# 08_-LoRa_RAK3172.net
KiCad netlist of a schematic drawn in Altium Designer
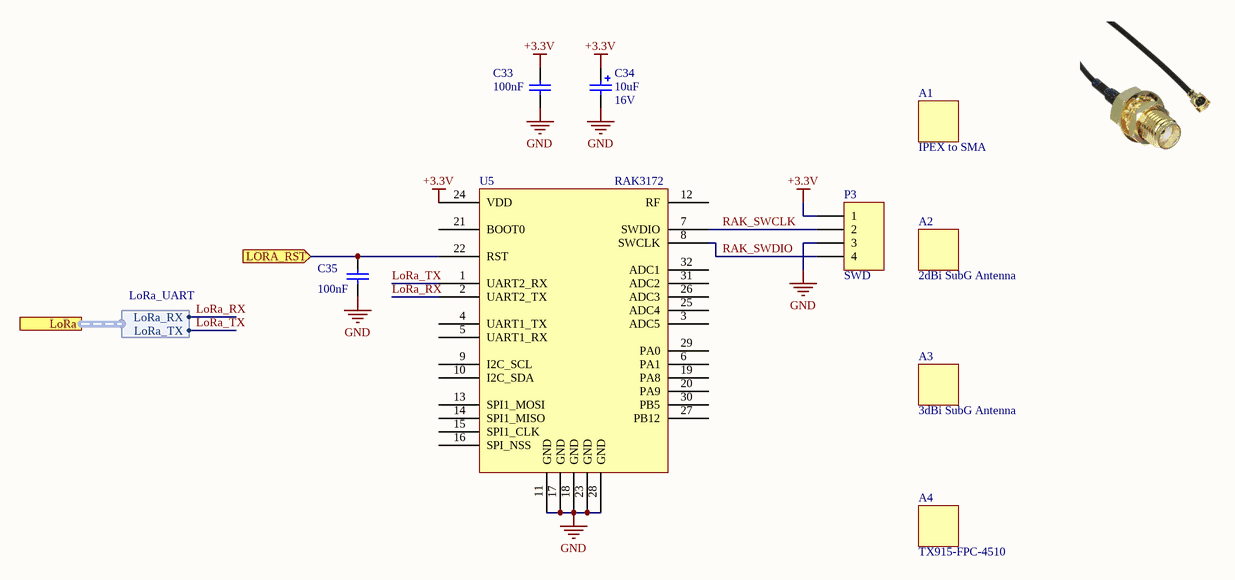
[diagram p0: [08] -LoRa_RAK3172.SchDoc]

(export (version "E")
  (design (tool "Eeschema 10.0.6"))
  (components
    (comp (ref "A1")
      (value "IPEX to SMA")
      (description "IPEX to SMA adapter cable")
      (libsource (lib "BaseNode v1.2") (part "Mechanical_component"))
    )
    (comp (ref "A2")
      (value "2dBi SubG Antenna")
      (libsource (lib "BaseNode v1.2") (part "Mechanical_component"))
    )
    (comp (ref "A3")
      (value "3dBi SubG Antenna")
      (libsource (lib "BaseNode v1.2") (part "Mechanical_component"))
    )
    (comp (ref "A4")
      (value "TX915-FPC-4510")
      (description "TX915-FPC-4510 868~930MHz adhesive antenna")
      (libsource (lib "BaseNode v1.2") (part "Mechanical_component"))
    )
    (comp (ref "C33")
      (value "Capacitor")
      (footprint "Cap 0603")
      (description "Cap Ceramic 0.1uF 50VDC X7R 10% SMD 0603 Paper T/R")
      (fields
        (field (name "MANUFACTURER") "Samsung")
        (field (name "MANUFACTURER PART NUMBER") "CL10B104KB8NNNC")
        (field (name "CAPACITANCE") "100nF")
      )
      (libsource (lib "Altium_Library") (part "Capacitor"))
    )
    (comp (ref "C34")
      (value "Capacitor Polarized")
      (footprint "Tantalum 3216 A")
      (description "CAP TANT 10UF 10% 16V 1206")
      (fields
        (field (name "MANUFACTURER") "Vishay Sprague")
        (field (name "MANUFACTURER PART NUMBER") "293D106X9016A2TE3")
        (field (name "CAPACITANCE") "10uF")
        (field (name "VOLTAGE RATING") "16V")
      )
      (libsource (lib "Altium_Library") (part "Capacitor Polarized"))
    )
    (comp (ref "C35")
      (value "Capacitor")
      (footprint "Cap 0603")
      (description "Cap Ceramic 0.1uF 50VDC X7R 10% SMD 0603 Paper T/R")
      (fields
        (field (name "MANUFACTURER") "Samsung")
        (field (name "MANUFACTURER PART NUMBER") "CL10B104KB8NNNC")
        (field (name "CAPACITANCE") "100nF")
      )
      (libsource (lib "Altium_Library") (part "Capacitor"))
    )
    (comp (ref "P3")
      (value "SWD")
      (footprint "HEADER SMD")
      (description "CONN HEADER VERT 4POS 2.54MM")
      (fields
        (field (name "MANUFACTURER") "Wurth Electronics")
        (field (name "MANUFACTURER PART NUMBER") "61300411121")
      )
      (libsource (lib "Altium_Library") (part "Header 4"))
    )
    (comp (ref "U5")
      (value "RAK3172")
      (footprint "RAK3172")
      (description "LPWAN Module")
      (libsource (lib "BaseNode v1.3") (part "RAK3172"))
    )
  )
  (nets
    (net (code "2") (name "+3.3V") (class "Default")
      (node (ref "C33") (pin "2") (pinfunction "2_2") (pintype "passive"))
      (node (ref "C34") (pin "1") (pinfunction "1_1") (pintype "passive"))
      (node (ref "P3") (pin "1") (pinfunction "1_1") (pintype "passive"))
      (node (ref "U5") (pin "24") (pinfunction "VDD_24") (pintype "passive"))
    )
    (net (code "3") (name "/LORA_RST") (class "Default")
      (node (ref "C35") (pin "2") (pinfunction "2_2") (pintype "passive"))
      (node (ref "U5") (pin "22") (pinfunction "RST_22") (pintype "passive"))
    )
    (net (code "4") (name "/LoRa_RX") (class "Default")
      (node (ref "U5") (pin "2") (pinfunction "UART2_TX_2") (pintype "passive"))
    )
    (net (code "5") (name "/LoRa_TX") (class "Default")
      (node (ref "U5") (pin "1") (pinfunction "UART2_RX_1") (pintype "passive"))
    )
    (net (code "6") (name "/RAK_SWCLK") (class "Default")
      (node (ref "P3") (pin "2") (pinfunction "2_2") (pintype "passive"))
      (node (ref "U5") (pin "7") (pinfunction "SWDIO_7") (pintype "passive"))
    )
    (net (code "7") (name "/RAK_SWDIO") (class "Default")
      (node (ref "P3") (pin "4") (pinfunction "4_4") (pintype "passive"))
      (node (ref "U5") (pin "8") (pinfunction "SWCLK_8") (pintype "passive"))
    )
    (net (code "9") (name "GND") (class "Default")
      (node (ref "C33") (pin "1") (pinfunction "1_1") (pintype "passive"))
      (node (ref "C34") (pin "2") (pinfunction "2_2") (pintype "passive"))
      (node (ref "C35") (pin "1") (pinfunction "1_1") (pintype "passive"))
      (node (ref "P3") (pin "3") (pinfunction "3_3") (pintype "passive"))
      (node (ref "U5") (pin "11") (pinfunction "GND_11") (pintype "passive"))
      (node (ref "U5") (pin "17") (pinfunction "GND_17") (pintype "passive"))
      (node (ref "U5") (pin "18") (pinfunction "GND_18") (pintype "passive"))
      (node (ref "U5") (pin "23") (pinfunction "GND_23") (pintype "passive"))
      (node (ref "U5") (pin "28") (pinfunction "GND_28") (pintype "passive"))
    )
    (net (code "10") (name "unconnected-(U5-ADC1-Pad32)") (class "Default")
      (node (ref "U5") (pin "32") (pinfunction "ADC1_32") (pintype "passive"))
    )
    (net (code "11") (name "unconnected-(U5-ADC2-Pad31)") (class "Default")
      (node (ref "U5") (pin "31") (pinfunction "ADC2_31") (pintype "passive"))
    )
    (net (code "12") (name "unconnected-(U5-ADC3-Pad26)") (class "Default")
      (node (ref "U5") (pin "26") (pinfunction "ADC3_26") (pintype "passive"))
    )
    (net (code "13") (name "unconnected-(U5-ADC4-Pad25)") (class "Default")
      (node (ref "U5") (pin "25") (pinfunction "ADC4_25") (pintype "passive"))
    )
    (net (code "14") (name "unconnected-(U5-ADC5-Pad3)") (class "Default")
      (node (ref "U5") (pin "3") (pinfunction "ADC5_3") (pintype "passive"))
    )
    (net (code "15") (name "unconnected-(U5-BOOT0-Pad21)") (class "Default")
      (node (ref "U5") (pin "21") (pinfunction "BOOT0_21") (pintype "passive"))
    )
    (net (code "16") (name "unconnected-(U5-I2C_SCL-Pad9)") (class "Default")
      (node (ref "U5") (pin "9") (pinfunction "I2C_SCL_9") (pintype "passive"))
    )
    (net (code "17") (name "unconnected-(U5-I2C_SDA-Pad10)") (class "Default")
      (node (ref "U5") (pin "10") (pinfunction "I2C_SDA_10") (pintype "passive"))
    )
    (net (code "18") (name "unconnected-(U5-PA0-Pad29)") (class "Default")
      (node (ref "U5") (pin "29") (pinfunction "PA0_29") (pintype "passive"))
    )
    (net (code "19") (name "unconnected-(U5-PA1-Pad6)") (class "Default")
      (node (ref "U5") (pin "6") (pinfunction "PA1_6") (pintype "passive"))
    )
    (net (code "20") (name "unconnected-(U5-PA8-Pad19)") (class "Default")
      (node (ref "U5") (pin "19") (pinfunction "PA8_19") (pintype "passive"))
    )
    (net (code "21") (name "unconnected-(U5-PA9-Pad20)") (class "Default")
      (node (ref "U5") (pin "20") (pinfunction "PA9_20") (pintype "passive"))
    )
    (net (code "22") (name "unconnected-(U5-PB5-Pad30)") (class "Default")
      (node (ref "U5") (pin "30") (pinfunction "PB5_30") (pintype "passive"))
    )
    (net (code "23") (name "unconnected-(U5-PB12-Pad27)") (class "Default")
      (node (ref "U5") (pin "27") (pinfunction "PB12_27") (pintype "passive"))
    )
    (net (code "24") (name "unconnected-(U5-RF-Pad12)") (class "Default")
      (node (ref "U5") (pin "12") (pinfunction "RF_12") (pintype "passive"))
    )
    (net (code "25") (name "unconnected-(U5-SPI1_CLK-Pad15)") (class "Default")
      (node (ref "U5") (pin "15") (pinfunction "SPI1_CLK_15") (pintype "passive"))
    )
    (net (code "26") (name "unconnected-(U5-SPI1_MISO-Pad14)") (class "Default")
      (node (ref "U5") (pin "14") (pinfunction "SPI1_MISO_14") (pintype "passive"))
    )
    (net (code "27") (name "unconnected-(U5-SPI1_MOSI-Pad13)") (class "Default")
      (node (ref "U5") (pin "13") (pinfunction "SPI1_MOSI_13") (pintype "passive"))
    )
    (net (code "28") (name "unconnected-(U5-SPI_NSS-Pad16)") (class "Default")
      (node (ref "U5") (pin "16") (pinfunction "SPI_NSS_16") (pintype "passive"))
    )
    (net (code "29") (name "unconnected-(U5-UART1_RX-Pad5)") (class "Default")
      (node (ref "U5") (pin "5") (pinfunction "UART1_RX_5") (pintype "passive"))
    )
    (net (code "30") (name "unconnected-(U5-UART1_TX-Pad4)") (class "Default")
      (node (ref "U5") (pin "4") (pinfunction "UART1_TX_4") (pintype "passive"))
    )
  )
)
